# controller12lcd.net
KiCad netlist of a schematic drawn in EAGLE
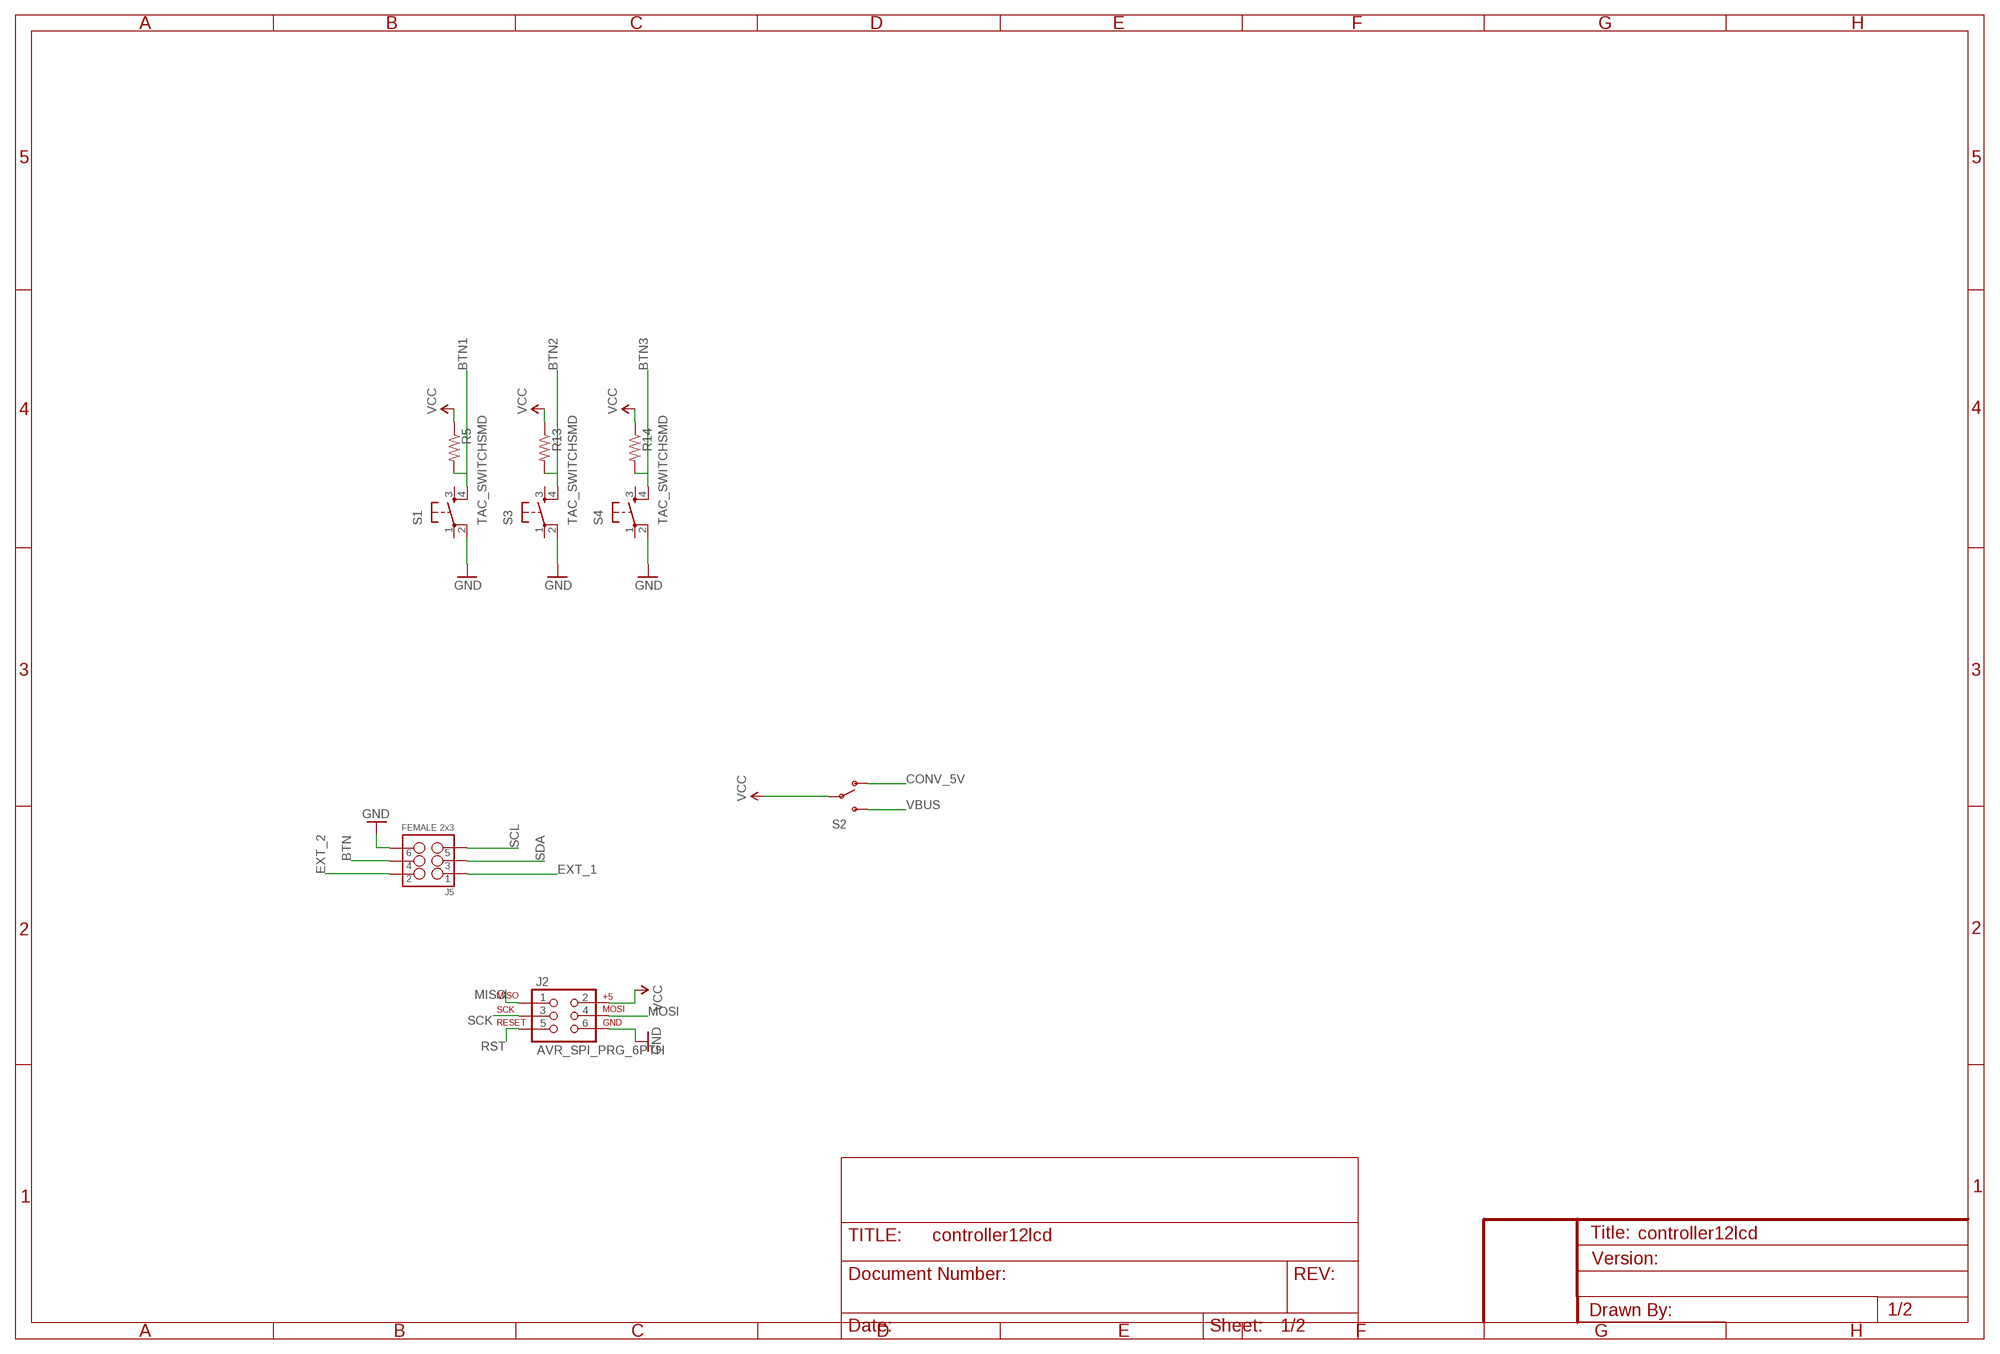
[diagram p0: schematic, sheet 1]
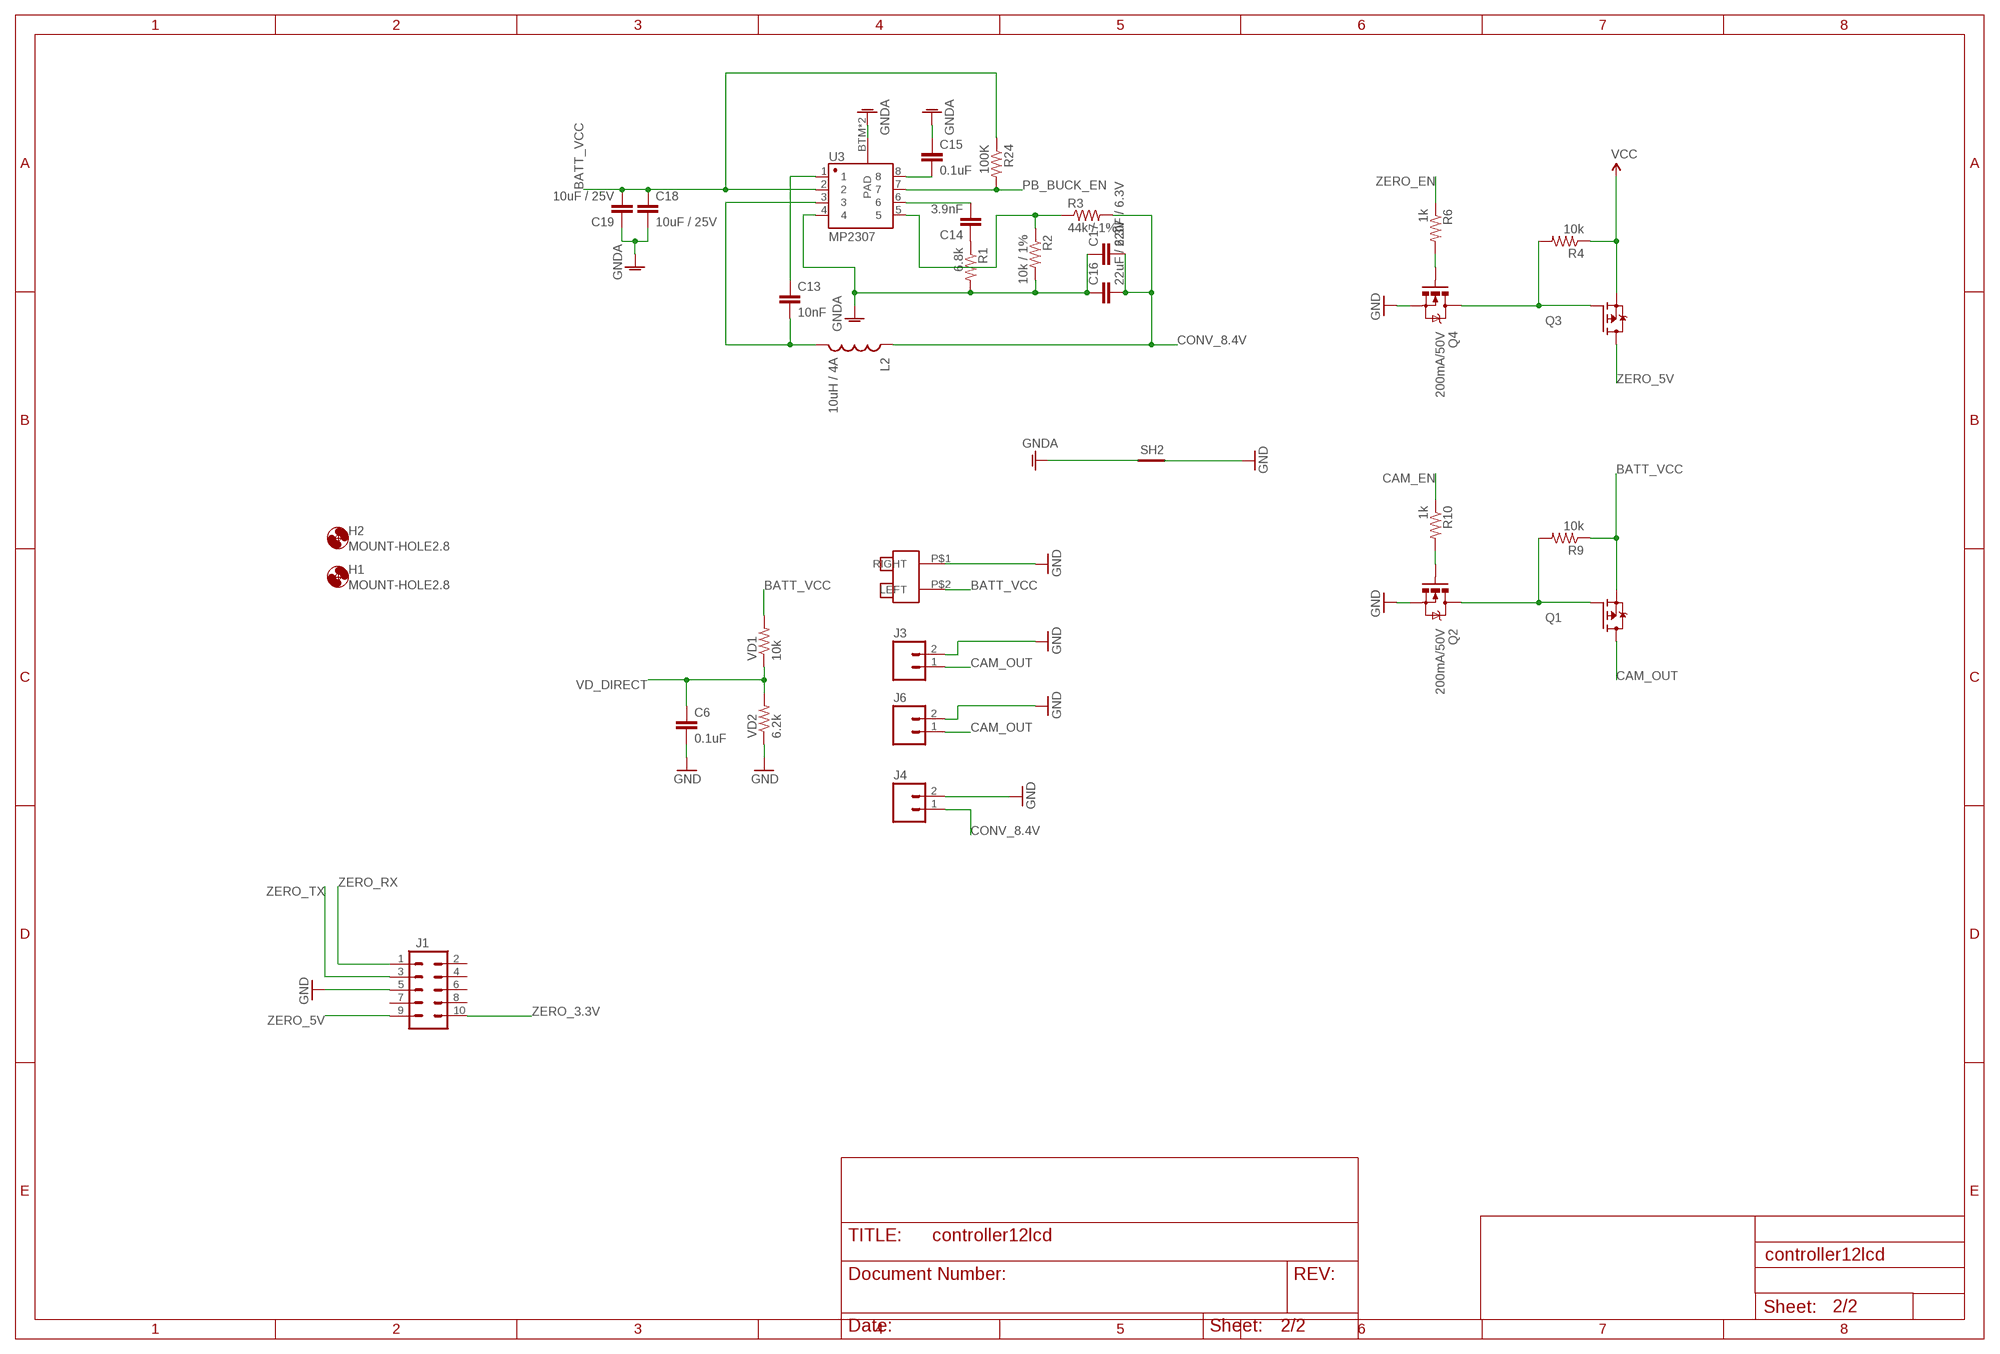
[diagram p1: schematic, sheet 2]

(export (version "E")
  (design (tool "Eeschema 10.0.6"))
  (components
    (comp (ref "J2")
      (value "AVR_SPI_PRG_6PTH")
      (footprint "eagle-import:2X3")
      (libsource (lib "eagle-import") (part "AVR_SPI_PRG_6PTH"))
    )
    (comp (ref "J5")
      (value "FEMALE 2x3")
      (footprint "eagle-import:2X3")
      (libsource (lib "eagle-import") (part "M03X2FEMALE"))
    )
    (comp (ref "R5")
      (value "RESISTOR1206")
      (footprint "eagle-import:1206")
      (libsource (lib "eagle-import") (part "RESISTOR1206"))
    )
    (comp (ref "R13")
      (value "RESISTOR1206")
      (footprint "eagle-import:1206")
      (libsource (lib "eagle-import") (part "RESISTOR1206"))
    )
    (comp (ref "R14")
      (value "RESISTOR1206")
      (footprint "eagle-import:1206")
      (libsource (lib "eagle-import") (part "RESISTOR1206"))
    )
    (comp (ref "S1")
      (value "TAC_SWITCHSMD")
      (footprint "eagle-import:TACTILE-PTH")
      (libsource (lib "eagle-import") (part "TAC_SWITCHPTH"))
    )
    (comp (ref "S2")
      (value "SWITCH-SPDTSMD2")
      (footprint "eagle-import:SWITCH-SPDT-SMD")
      (libsource (lib "eagle-import") (part "SWITCH-SPDTSMD2"))
    )
    (comp (ref "S3")
      (value "TAC_SWITCHSMD")
      (footprint "eagle-import:TACTILE-PTH")
      (libsource (lib "eagle-import") (part "TAC_SWITCHPTH"))
    )
    (comp (ref "S4")
      (value "TAC_SWITCHSMD")
      (footprint "eagle-import:TACTILE-PTH")
      (libsource (lib "eagle-import") (part "TAC_SWITCHPTH"))
    )
    (comp (ref "C6")
      (value "0.1uF")
      (footprint "eagle-import:1206")
      (libsource (lib "eagle-import") (part "CAP1206"))
    )
    (comp (ref "C13")
      (value "10nF")
      (footprint "eagle-import:1206")
      (libsource (lib "eagle-import") (part "CAP1206"))
    )
    (comp (ref "C14")
      (value "3.9nF")
      (footprint "eagle-import:1206")
      (libsource (lib "eagle-import") (part "CAP1206"))
    )
    (comp (ref "C15")
      (value "0.1uF")
      (footprint "eagle-import:1206")
      (libsource (lib "eagle-import") (part "CAP1206"))
    )
    (comp (ref "C16")
      (value "22uF / 6.3V")
      (footprint "eagle-import:1210")
      (libsource (lib "eagle-import") (part "CAP1210"))
    )
    (comp (ref "C17")
      (value "22uF / 6.3V")
      (footprint "eagle-import:1210")
      (libsource (lib "eagle-import") (part "CAP1210"))
    )
    (comp (ref "C18")
      (value "10uF / 25V")
      (footprint "eagle-import:1210")
      (libsource (lib "eagle-import") (part "CAP1210"))
    )
    (comp (ref "C19")
      (value "10uF / 25V")
      (footprint "eagle-import:1210")
      (libsource (lib "eagle-import") (part "CAP1210"))
    )
    (comp (ref "H1")
      (value "MOUNT-HOLE2.8")
      (footprint "eagle-import:2,8")
      (libsource (lib "eagle-import") (part "MOUNT-HOLE2.8"))
    )
    (comp (ref "H2")
      (value "MOUNT-HOLE2.8")
      (footprint "eagle-import:2,8")
      (libsource (lib "eagle-import") (part "MOUNT-HOLE2.8"))
    )
    (comp (ref "J1")
      (value "M05X2PTH")
      (footprint "eagle-import:AVR_ICSP")
      (libsource (lib "eagle-import") (part "M05X2PTH"))
    )
    (comp (ref "J3")
      (value "M023.5MM_LOCK")
      (footprint "eagle-import:SCREWTERMINAL-3.5MM-2_LOCK")
      (libsource (lib "eagle-import") (part "M023.5MM_LOCK"))
    )
    (comp (ref "J4")
      (value "M02PTH")
      (footprint "eagle-import:1X02")
      (libsource (lib "eagle-import") (part "M02PTH"))
    )
    (comp (ref "J6")
      (value "M023.5MM_LOCK")
      (footprint "eagle-import:SCREWTERMINAL-3.5MM-2_LOCK")
      (libsource (lib "eagle-import") (part "M023.5MM_LOCK"))
    )
    (comp (ref "L2")
      (value "10uH / 4A")
      (footprint "eagle-import:SRU1038")
      (libsource (lib "eagle-import") (part "INDUCTORSRU1038"))
    )
    (comp (ref "Q1")
      (value "FDD4141TO252")
      (footprint "eagle-import:TO252")
      (libsource (lib "eagle-import") (part "FDD4141TO252"))
    )
    (comp (ref "Q2")
      (value "200mA/50V")
      (footprint "eagle-import:SOT23-3")
      (libsource (lib "eagle-import") (part "MOSFET-NCHANNELBSS138"))
    )
    (comp (ref "Q3")
      (value "FDD4141TO252")
      (footprint "eagle-import:TO252")
      (libsource (lib "eagle-import") (part "FDD4141TO252"))
    )
    (comp (ref "Q4")
      (value "200mA/50V")
      (footprint "eagle-import:SOT23-3")
      (libsource (lib "eagle-import") (part "MOSFET-NCHANNELBSS138"))
    )
    (comp (ref "R1")
      (value "6.8k")
      (footprint "eagle-import:1206")
      (libsource (lib "eagle-import") (part "SparkFun-Resistors_RESISTOR1206"))
    )
    (comp (ref "R2")
      (value "10k / 1%")
      (footprint "eagle-import:1206")
      (libsource (lib "eagle-import") (part "SparkFun-Resistors_RESISTOR1206"))
    )
    (comp (ref "R3")
      (value "44k / 1%")
      (footprint "eagle-import:1206")
      (libsource (lib "eagle-import") (part "SparkFun-Resistors_RESISTOR1206"))
    )
    (comp (ref "R4")
      (value "10k")
      (footprint "eagle-import:1206")
      (libsource (lib "eagle-import") (part "SparkFun-Resistors_RESISTOR1206"))
    )
    (comp (ref "R6")
      (value "1k")
      (footprint "eagle-import:1206")
      (libsource (lib "eagle-import") (part "SparkFun-Resistors_RESISTOR1206"))
    )
    (comp (ref "R9")
      (value "10k")
      (footprint "eagle-import:1206")
      (libsource (lib "eagle-import") (part "SparkFun-Resistors_RESISTOR1206"))
    )
    (comp (ref "R10")
      (value "1k")
      (footprint "eagle-import:1206")
      (libsource (lib "eagle-import") (part "SparkFun-Resistors_RESISTOR1206"))
    )
    (comp (ref "R24")
      (value "100K")
      (footprint "eagle-import:1206")
      (libsource (lib "eagle-import") (part "SparkFun-Resistors_RESISTOR1206"))
    )
    (comp (ref "SH2")
      (value "SHORT-HT5")
      (footprint "eagle-import:SHORT_TOP-50")
      (libsource (lib "eagle-import") (part "SHORT-HT5"))
    )
    (comp (ref "U$4")
      (value "NANOFIT2")
      (footprint "eagle-import:NANOFIT2")
      (libsource (lib "eagle-import") (part "NANOFIT2"))
    )
    (comp (ref "U3")
      (value "MP2307")
      (footprint "eagle-import:SO08")
      (libsource (lib "eagle-import") (part "GENERIC-SOIC8MSGEQ7N-FILTER"))
    )
    (comp (ref "VD1")
      (value "10k")
      (footprint "eagle-import:1206")
      (libsource (lib "eagle-import") (part "RESISTOR1206"))
    )
    (comp (ref "VD2")
      (value "6.2k")
      (footprint "eagle-import:1206")
      (libsource (lib "eagle-import") (part "RESISTOR1206"))
    )
  )
  (nets
    (net (code "1") (name "BATT_VCC") (class "Default")
      (node (ref "C18") (pin "1") (pinfunction "1_1") (pintype "passive"))
      (node (ref "C19") (pin "2") (pinfunction "2_2") (pintype "passive"))
      (node (ref "Q1") (pin "2") (pinfunction "S_2") (pintype "passive"))
      (node (ref "R24") (pin "1") (pinfunction "1_1") (pintype "passive"))
      (node (ref "R9") (pin "1") (pinfunction "1_1") (pintype "passive"))
      (node (ref "U$4") (pin "P$2") (pinfunction "LEFT_P$2") (pintype "bidirectional"))
      (node (ref "U3") (pin "2") (pinfunction "2_2") (pintype "bidirectional"))
      (node (ref "VD1") (pin "2") (pinfunction "2_2") (pintype "passive"))
    )
    (net (code "2") (name "BTN") (class "Default")
      (node (ref "J5") (pin "4") (pinfunction "4_4") (pintype "bidirectional"))
    )
    (net (code "3") (name "BTN1") (class "Default")
      (node (ref "R5") (pin "2") (pinfunction "2_2") (pintype "passive"))
      (node (ref "S1") (pin "4") (pinfunction "4_4") (pintype "passive"))
    )
    (net (code "4") (name "BTN2") (class "Default")
      (node (ref "R13") (pin "2") (pinfunction "2_2") (pintype "passive"))
      (node (ref "S3") (pin "4") (pinfunction "4_4") (pintype "passive"))
    )
    (net (code "5") (name "BTN3") (class "Default")
      (node (ref "R14") (pin "2") (pinfunction "2_2") (pintype "passive"))
      (node (ref "S4") (pin "4") (pinfunction "4_4") (pintype "passive"))
    )
    (net (code "6") (name "CAM_EN") (class "Default")
      (node (ref "R10") (pin "1") (pinfunction "1_1") (pintype "passive"))
    )
    (net (code "7") (name "CAM_OUT") (class "Default")
      (node (ref "J3") (pin "1") (pinfunction "1_1") (pintype "passive"))
      (node (ref "J6") (pin "1") (pinfunction "1_1") (pintype "passive"))
      (node (ref "Q1") (pin "3") (pinfunction "D_3") (pintype "passive"))
    )
    (net (code "8") (name "CONV_5V") (class "Default")
      (node (ref "S2") (pin "1") (pinfunction "O_1") (pintype "passive"))
    )
    (net (code "9") (name "CONV_8.4V") (class "Default")
      (node (ref "C16") (pin "2") (pinfunction "2_2") (pintype "passive"))
      (node (ref "C17") (pin "2") (pinfunction "2_2") (pintype "passive"))
      (node (ref "J4") (pin "1") (pinfunction "1_1") (pintype "passive"))
      (node (ref "L2") (pin "1") (pinfunction "1_1") (pintype "passive"))
      (node (ref "R3") (pin "2") (pinfunction "2_2") (pintype "passive"))
    )
    (net (code "10") (name "EXT_1") (class "Default")
      (node (ref "J5") (pin "1") (pinfunction "1_1") (pintype "bidirectional"))
    )
    (net (code "11") (name "EXT_2") (class "Default")
      (node (ref "J5") (pin "2") (pinfunction "2_2") (pintype "bidirectional"))
    )
    (net (code "12") (name "GND") (class "Default")
      (node (ref "C6") (pin "2") (pinfunction "2_2") (pintype "passive"))
      (node (ref "J1") (pin "5") (pinfunction "5_5") (pintype "passive"))
      (node (ref "J2") (pin "6") (pinfunction "6_6") (pintype "passive"))
      (node (ref "J3") (pin "2") (pinfunction "2_2") (pintype "passive"))
      (node (ref "J4") (pin "2") (pinfunction "2_2") (pintype "passive"))
      (node (ref "J5") (pin "6") (pinfunction "6_6") (pintype "bidirectional"))
      (node (ref "J6") (pin "2") (pinfunction "2_2") (pintype "passive"))
      (node (ref "Q2") (pin "2") (pinfunction "S_2") (pintype "passive"))
      (node (ref "Q4") (pin "2") (pinfunction "S_2") (pintype "passive"))
      (node (ref "S1") (pin "2") (pinfunction "2_2") (pintype "passive"))
      (node (ref "S3") (pin "2") (pinfunction "2_2") (pintype "passive"))
      (node (ref "S4") (pin "2") (pinfunction "2_2") (pintype "passive"))
      (node (ref "SH2") (pin "2") (pinfunction "P$2_2") (pintype "bidirectional"))
      (node (ref "U$4") (pin "P$1") (pinfunction "RIGHT_P$1") (pintype "bidirectional"))
      (node (ref "VD2") (pin "1") (pinfunction "1_1") (pintype "passive"))
    )
    (net (code "13") (name "GNDA") (class "Default")
      (node (ref "C15") (pin "1") (pinfunction "1_1") (pintype "passive"))
      (node (ref "C16") (pin "1") (pinfunction "1_1") (pintype "passive"))
      (node (ref "C17") (pin "1") (pinfunction "1_1") (pintype "passive"))
      (node (ref "C18") (pin "2") (pinfunction "2_2") (pintype "passive"))
      (node (ref "C19") (pin "1") (pinfunction "1_1") (pintype "passive"))
      (node (ref "R1") (pin "2") (pinfunction "2_2") (pintype "passive"))
      (node (ref "R2") (pin "2") (pinfunction "2_2") (pintype "passive"))
      (node (ref "SH2") (pin "1") (pinfunction "P$1_1") (pintype "bidirectional"))
      (node (ref "U3") (pin "4") (pinfunction "4_4") (pintype "bidirectional"))
      (node (ref "U3") (pin "BTM") (pinfunction "PAD_BTM") (pintype "bidirectional"))
      (node (ref "U3") (pin "P$1") (pinfunction "PAD_P$1") (pintype "bidirectional"))
    )
    (net (code "14") (name "MISO") (class "Default")
      (node (ref "J2") (pin "1") (pinfunction "1_1") (pintype "passive"))
    )
    (net (code "15") (name "MOSI") (class "Default")
      (node (ref "J2") (pin "4") (pinfunction "4_4") (pintype "passive"))
    )
    (net (code "16") (name "Net-(C13-Pad1)") (class "Default")
      (node (ref "C13") (pin "1") (pinfunction "1_1") (pintype "passive"))
      (node (ref "U3") (pin "1") (pinfunction "1_1") (pintype "bidirectional"))
    )
    (net (code "17") (name "Net-(C13-Pad2)") (class "Default")
      (node (ref "C13") (pin "2") (pinfunction "2_2") (pintype "passive"))
      (node (ref "L2") (pin "2") (pinfunction "2_2") (pintype "passive"))
      (node (ref "U3") (pin "3") (pinfunction "3_3") (pintype "bidirectional"))
    )
    (net (code "18") (name "Net-(C14-Pad1)") (class "Default")
      (node (ref "C14") (pin "1") (pinfunction "1_1") (pintype "passive"))
      (node (ref "R1") (pin "1") (pinfunction "1_1") (pintype "passive"))
    )
    (net (code "19") (name "Net-(C14-Pad2)") (class "Default")
      (node (ref "C14") (pin "2") (pinfunction "2_2") (pintype "passive"))
      (node (ref "U3") (pin "6") (pinfunction "6_6") (pintype "bidirectional"))
    )
    (net (code "20") (name "Net-(C15-Pad2)") (class "Default")
      (node (ref "C15") (pin "2") (pinfunction "2_2") (pintype "passive"))
      (node (ref "U3") (pin "8") (pinfunction "8_8") (pintype "bidirectional"))
    )
    (net (code "21") (name "Net-(Q1-G)") (class "Default")
      (node (ref "Q1") (pin "1") (pinfunction "G_1") (pintype "passive"))
      (node (ref "Q2") (pin "3") (pinfunction "D_3") (pintype "passive"))
      (node (ref "R9") (pin "2") (pinfunction "2_2") (pintype "passive"))
    )
    (net (code "22") (name "Net-(Q2-G)") (class "Default")
      (node (ref "Q2") (pin "1") (pinfunction "G_1") (pintype "passive"))
      (node (ref "R10") (pin "2") (pinfunction "2_2") (pintype "passive"))
    )
    (net (code "23") (name "Net-(Q3-G)") (class "Default")
      (node (ref "Q3") (pin "1") (pinfunction "G_1") (pintype "passive"))
      (node (ref "Q4") (pin "3") (pinfunction "D_3") (pintype "passive"))
      (node (ref "R4") (pin "2") (pinfunction "2_2") (pintype "passive"))
    )
    (net (code "24") (name "Net-(Q4-G)") (class "Default")
      (node (ref "Q4") (pin "1") (pinfunction "G_1") (pintype "passive"))
      (node (ref "R6") (pin "2") (pinfunction "2_2") (pintype "passive"))
    )
    (net (code "25") (name "Net-(R2-Pad1)") (class "Default")
      (node (ref "R2") (pin "1") (pinfunction "1_1") (pintype "passive"))
      (node (ref "R3") (pin "1") (pinfunction "1_1") (pintype "passive"))
      (node (ref "U3") (pin "5") (pinfunction "5_5") (pintype "bidirectional"))
    )
    (net (code "26") (name "PB_BUCK_EN") (class "Default")
      (node (ref "R24") (pin "2") (pinfunction "2_2") (pintype "passive"))
      (node (ref "U3") (pin "7") (pinfunction "7_7") (pintype "bidirectional"))
    )
    (net (code "27") (name "RST") (class "Default")
      (node (ref "J2") (pin "5") (pinfunction "5_5") (pintype "passive"))
    )
    (net (code "28") (name "SCK") (class "Default")
      (node (ref "J2") (pin "3") (pinfunction "3_3") (pintype "passive"))
    )
    (net (code "29") (name "SCL") (class "Default")
      (node (ref "J5") (pin "5") (pinfunction "5_5") (pintype "bidirectional"))
    )
    (net (code "30") (name "SDA") (class "Default")
      (node (ref "J5") (pin "3") (pinfunction "3_3") (pintype "bidirectional"))
    )
    (net (code "31") (name "VBUS") (class "Default")
      (node (ref "S2") (pin "3") (pinfunction "S_3") (pintype "passive"))
    )
    (net (code "32") (name "VCC") (class "Default")
      (node (ref "J2") (pin "2") (pinfunction "2_2") (pintype "passive"))
      (node (ref "Q3") (pin "2") (pinfunction "S_2") (pintype "passive"))
      (node (ref "R13") (pin "1") (pinfunction "1_1") (pintype "passive"))
      (node (ref "R14") (pin "1") (pinfunction "1_1") (pintype "passive"))
      (node (ref "R4") (pin "1") (pinfunction "1_1") (pintype "passive"))
      (node (ref "R5") (pin "1") (pinfunction "1_1") (pintype "passive"))
      (node (ref "S2") (pin "2") (pinfunction "P_2") (pintype "passive"))
    )
    (net (code "33") (name "VD_DIRECT") (class "Default")
      (node (ref "C6") (pin "1") (pinfunction "1_1") (pintype "passive"))
      (node (ref "VD1") (pin "1") (pinfunction "1_1") (pintype "passive"))
      (node (ref "VD2") (pin "2") (pinfunction "2_2") (pintype "passive"))
    )
    (net (code "34") (name "ZERO_3.3V") (class "Default")
      (node (ref "J1") (pin "10") (pinfunction "10_10") (pintype "passive"))
    )
    (net (code "35") (name "ZERO_5V") (class "Default")
      (node (ref "J1") (pin "9") (pinfunction "9_9") (pintype "passive"))
      (node (ref "Q3") (pin "3") (pinfunction "D_3") (pintype "passive"))
    )
    (net (code "36") (name "ZERO_EN") (class "Default")
      (node (ref "R6") (pin "1") (pinfunction "1_1") (pintype "passive"))
    )
    (net (code "37") (name "ZERO_RX") (class "Default")
      (node (ref "J1") (pin "1") (pinfunction "1_1") (pintype "passive"))
    )
    (net (code "38") (name "ZERO_TX") (class "Default")
      (node (ref "J1") (pin "3") (pinfunction "3_3") (pintype "passive"))
    )
    (net (code "39") (name "unconnected-(J1-Pad2)") (class "Default")
      (node (ref "J1") (pin "2") (pinfunction "2_2") (pintype "passive"))
    )
    (net (code "40") (name "unconnected-(J1-Pad4)") (class "Default")
      (node (ref "J1") (pin "4") (pinfunction "4_4") (pintype "passive"))
    )
    (net (code "41") (name "unconnected-(J1-Pad6)") (class "Default")
      (node (ref "J1") (pin "6") (pinfunction "6_6") (pintype "passive"))
    )
    (net (code "42") (name "unconnected-(J1-Pad7)") (class "Default")
      (node (ref "J1") (pin "7") (pinfunction "7_7") (pintype "passive"))
    )
    (net (code "43") (name "unconnected-(J1-Pad8)") (class "Default")
      (node (ref "J1") (pin "8") (pinfunction "8_8") (pintype "passive"))
    )
    (net (code "44") (name "unconnected-(S1-Pad1)") (class "Default")
      (node (ref "S1") (pin "1") (pinfunction "1_1") (pintype "passive"))
    )
    (net (code "45") (name "unconnected-(S1-Pad3)") (class "Default")
      (node (ref "S1") (pin "3") (pinfunction "3_3") (pintype "passive"))
    )
    (net (code "46") (name "unconnected-(S3-Pad1)") (class "Default")
      (node (ref "S3") (pin "1") (pinfunction "1_1") (pintype "passive"))
    )
    (net (code "47") (name "unconnected-(S3-Pad3)") (class "Default")
      (node (ref "S3") (pin "3") (pinfunction "3_3") (pintype "passive"))
    )
    (net (code "48") (name "unconnected-(S4-Pad1)") (class "Default")
      (node (ref "S4") (pin "1") (pinfunction "1_1") (pintype "passive"))
    )
    (net (code "49") (name "unconnected-(S4-Pad3)") (class "Default")
      (node (ref "S4") (pin "3") (pinfunction "3_3") (pintype "passive"))
    )
  )
)
